# TEMP.net
KiCad netlist of a schematic drawn in Altium Designer
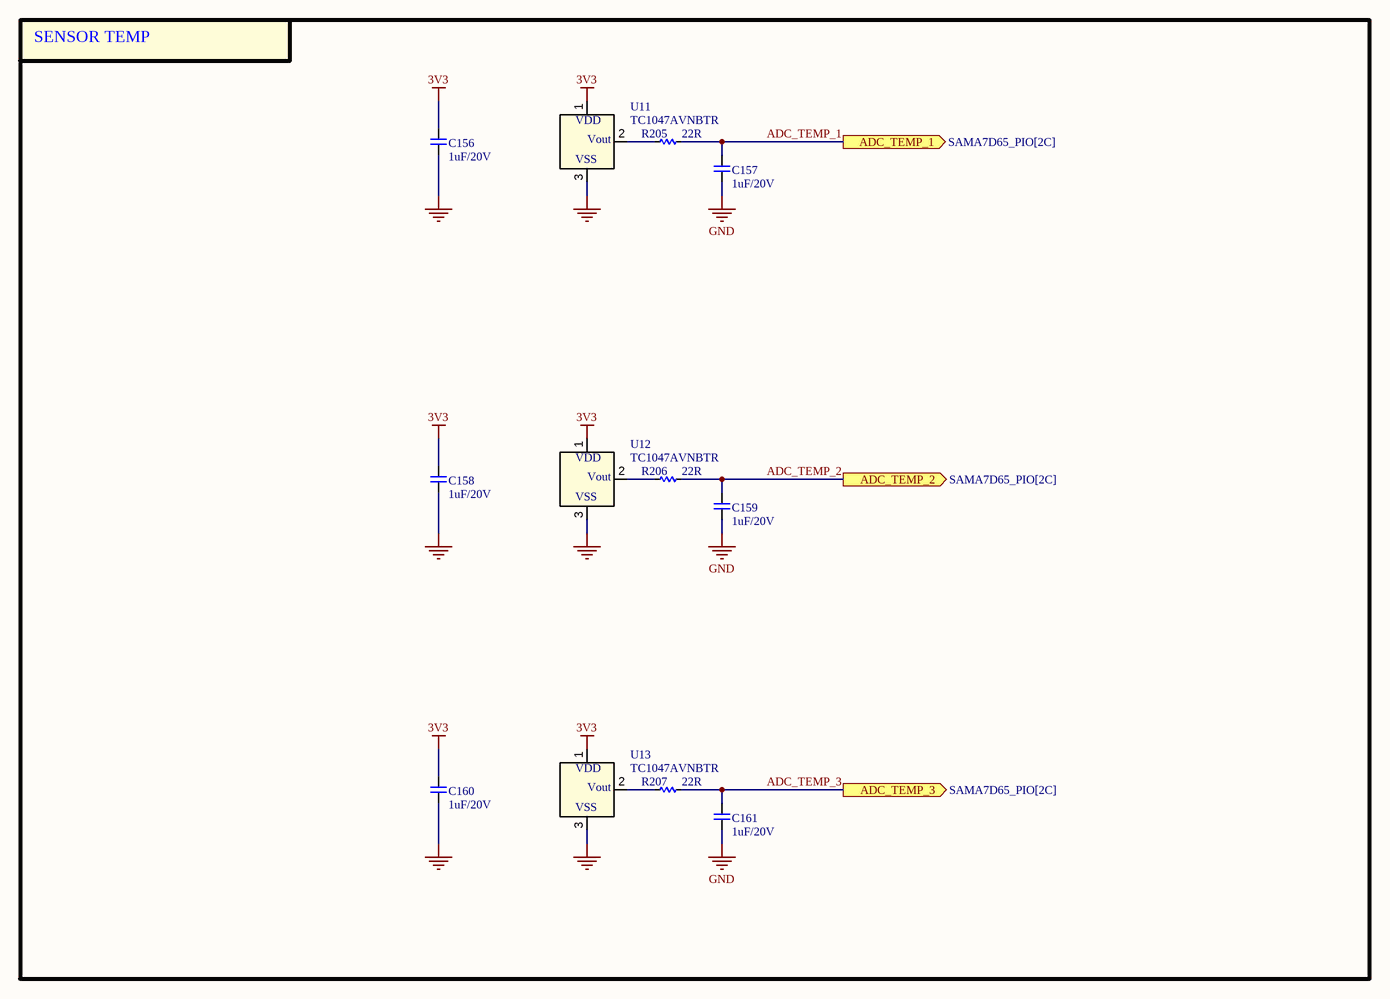
[diagram p0: TEMP.SchDoc]

(export (version "E")
  (design (tool "Eeschema 10.0.6"))
  (components
    (comp (ref "C156")
      (value "1uF/20V")
      (footprint "CAP_C_1005X50_L")
      (description "CAP CHIP")
      (libsource (lib "IFBschelib") (part "_CAP_C_2"))
    )
    (comp (ref "C157")
      (value "1uF/20V")
      (footprint "CAP_C_1005X50_L")
      (description "CAP CHIP")
      (libsource (lib "IFBschelib") (part "_CAP_C_2"))
    )
    (comp (ref "C158")
      (value "1uF/20V")
      (footprint "CAP_C_1005X50_L")
      (description "CAP CHIP")
      (libsource (lib "IFBschelib") (part "_CAP_C_2"))
    )
    (comp (ref "C159")
      (value "1uF/20V")
      (footprint "CAP_C_1005X50_L")
      (description "CAP CHIP")
      (libsource (lib "IFBschelib") (part "_CAP_C_2"))
    )
    (comp (ref "C160")
      (value "1uF/20V")
      (footprint "CAP_C_1005X50_L")
      (description "CAP CHIP")
      (libsource (lib "IFBschelib") (part "_CAP_C_2"))
    )
    (comp (ref "C161")
      (value "1uF/20V")
      (footprint "CAP_C_1005X50_L")
      (description "CAP CHIP")
      (libsource (lib "IFBschelib") (part "_CAP_C_2"))
    )
    (comp (ref "R205")
      (value "22R")
      (footprint "RES_C_1005x30_L")
      (description "RES")
      (libsource (lib "IFBschelib") (part "_RES_B_2"))
    )
    (comp (ref "R206")
      (value "22R")
      (footprint "RES_C_1005x30_L")
      (description "RES")
      (libsource (lib "IFBschelib") (part "_RES_B_2"))
    )
    (comp (ref "R207")
      (value "22R")
      (footprint "RES_C_1005x30_L")
      (description "RES")
      (libsource (lib "IFBschelib") (part "_RES_B_2"))
    )
    (comp (ref "U11")
      (value "TC1047AVNBTR")
      (footprint "SOT-23_MC_MCH")
      (description "SENSOR ANALOG -40C-125C SOT23-3")
      (fields (field (name "COPYRIGHT") "Copyright (C) 2025 Ultra Librarian. All rights reserved."))
      (libsource (lib "IFBschelib") (part "TC1047AVNBTR"))
    )
    (comp (ref "U12")
      (value "TC1047AVNBTR")
      (footprint "SOT-23_MC_MCH")
      (description "SENSOR ANALOG -40C-125C SOT23-3")
      (fields (field (name "COPYRIGHT") "Copyright (C) 2025 Ultra Librarian. All rights reserved."))
      (libsource (lib "IFBschelib") (part "TC1047AVNBTR"))
    )
    (comp (ref "U13")
      (value "TC1047AVNBTR")
      (footprint "SOT-23_MC_MCH")
      (description "SENSOR ANALOG -40C-125C SOT23-3")
      (fields (field (name "COPYRIGHT") "Copyright (C) 2025 Ultra Librarian. All rights reserved."))
      (libsource (lib "IFBschelib") (part "TC1047AVNBTR"))
    )
  )
  (nets
    (net (code "1") (name "/ADC_TEMP_1") (class "Default")
      (node (ref "C157") (pin "2") (pinfunction "2_2") (pintype "passive"))
      (node (ref "R205") (pin "2") (pinfunction "2_2") (pintype "passive"))
    )
    (net (code "2") (name "/ADC_TEMP_2") (class "Default")
      (node (ref "C159") (pin "2") (pinfunction "2_2") (pintype "passive"))
      (node (ref "R206") (pin "2") (pinfunction "2_2") (pintype "passive"))
    )
    (net (code "3") (name "/ADC_TEMP_3") (class "Default")
      (node (ref "C161") (pin "2") (pinfunction "2_2") (pintype "passive"))
      (node (ref "R207") (pin "2") (pinfunction "2_2") (pintype "passive"))
    )
    (net (code "4") (name "3V3") (class "Default")
      (node (ref "C156") (pin "2") (pinfunction "2_2") (pintype "passive"))
      (node (ref "C158") (pin "2") (pinfunction "2_2") (pintype "passive"))
      (node (ref "C160") (pin "2") (pinfunction "2_2") (pintype "passive"))
      (node (ref "U11") (pin "1") (pinfunction "VDD_1") (pintype "passive"))
      (node (ref "U12") (pin "1") (pinfunction "VDD_1") (pintype "passive"))
      (node (ref "U13") (pin "1") (pinfunction "VDD_1") (pintype "passive"))
    )
    (net (code "5") (name "GND") (class "Default")
      (node (ref "C156") (pin "1") (pinfunction "1_1") (pintype "passive"))
      (node (ref "C157") (pin "1") (pinfunction "1_1") (pintype "passive"))
      (node (ref "C158") (pin "1") (pinfunction "1_1") (pintype "passive"))
      (node (ref "C159") (pin "1") (pinfunction "1_1") (pintype "passive"))
      (node (ref "C160") (pin "1") (pinfunction "1_1") (pintype "passive"))
      (node (ref "C161") (pin "1") (pinfunction "1_1") (pintype "passive"))
      (node (ref "U11") (pin "3") (pinfunction "VSS_3") (pintype "passive"))
      (node (ref "U12") (pin "3") (pinfunction "VSS_3") (pintype "passive"))
      (node (ref "U13") (pin "3") (pinfunction "VSS_3") (pintype "passive"))
    )
    (net (code "6") (name "Net-(U11-VOUT)") (class "Default")
      (node (ref "R205") (pin "1") (pinfunction "1_1") (pintype "passive"))
      (node (ref "U11") (pin "2") (pinfunction "VOUT_2") (pintype "passive"))
    )
    (net (code "7") (name "Net-(U12-VOUT)") (class "Default")
      (node (ref "R206") (pin "1") (pinfunction "1_1") (pintype "passive"))
      (node (ref "U12") (pin "2") (pinfunction "VOUT_2") (pintype "passive"))
    )
    (net (code "8") (name "Net-(U13-VOUT)") (class "Default")
      (node (ref "R207") (pin "1") (pinfunction "1_1") (pintype "passive"))
      (node (ref "U13") (pin "2") (pinfunction "VOUT_2") (pintype "passive"))
    )
  )
)
